# univ_3-2-5-x-rev4.net
KiCad netlist of a schematic drawn in EAGLE
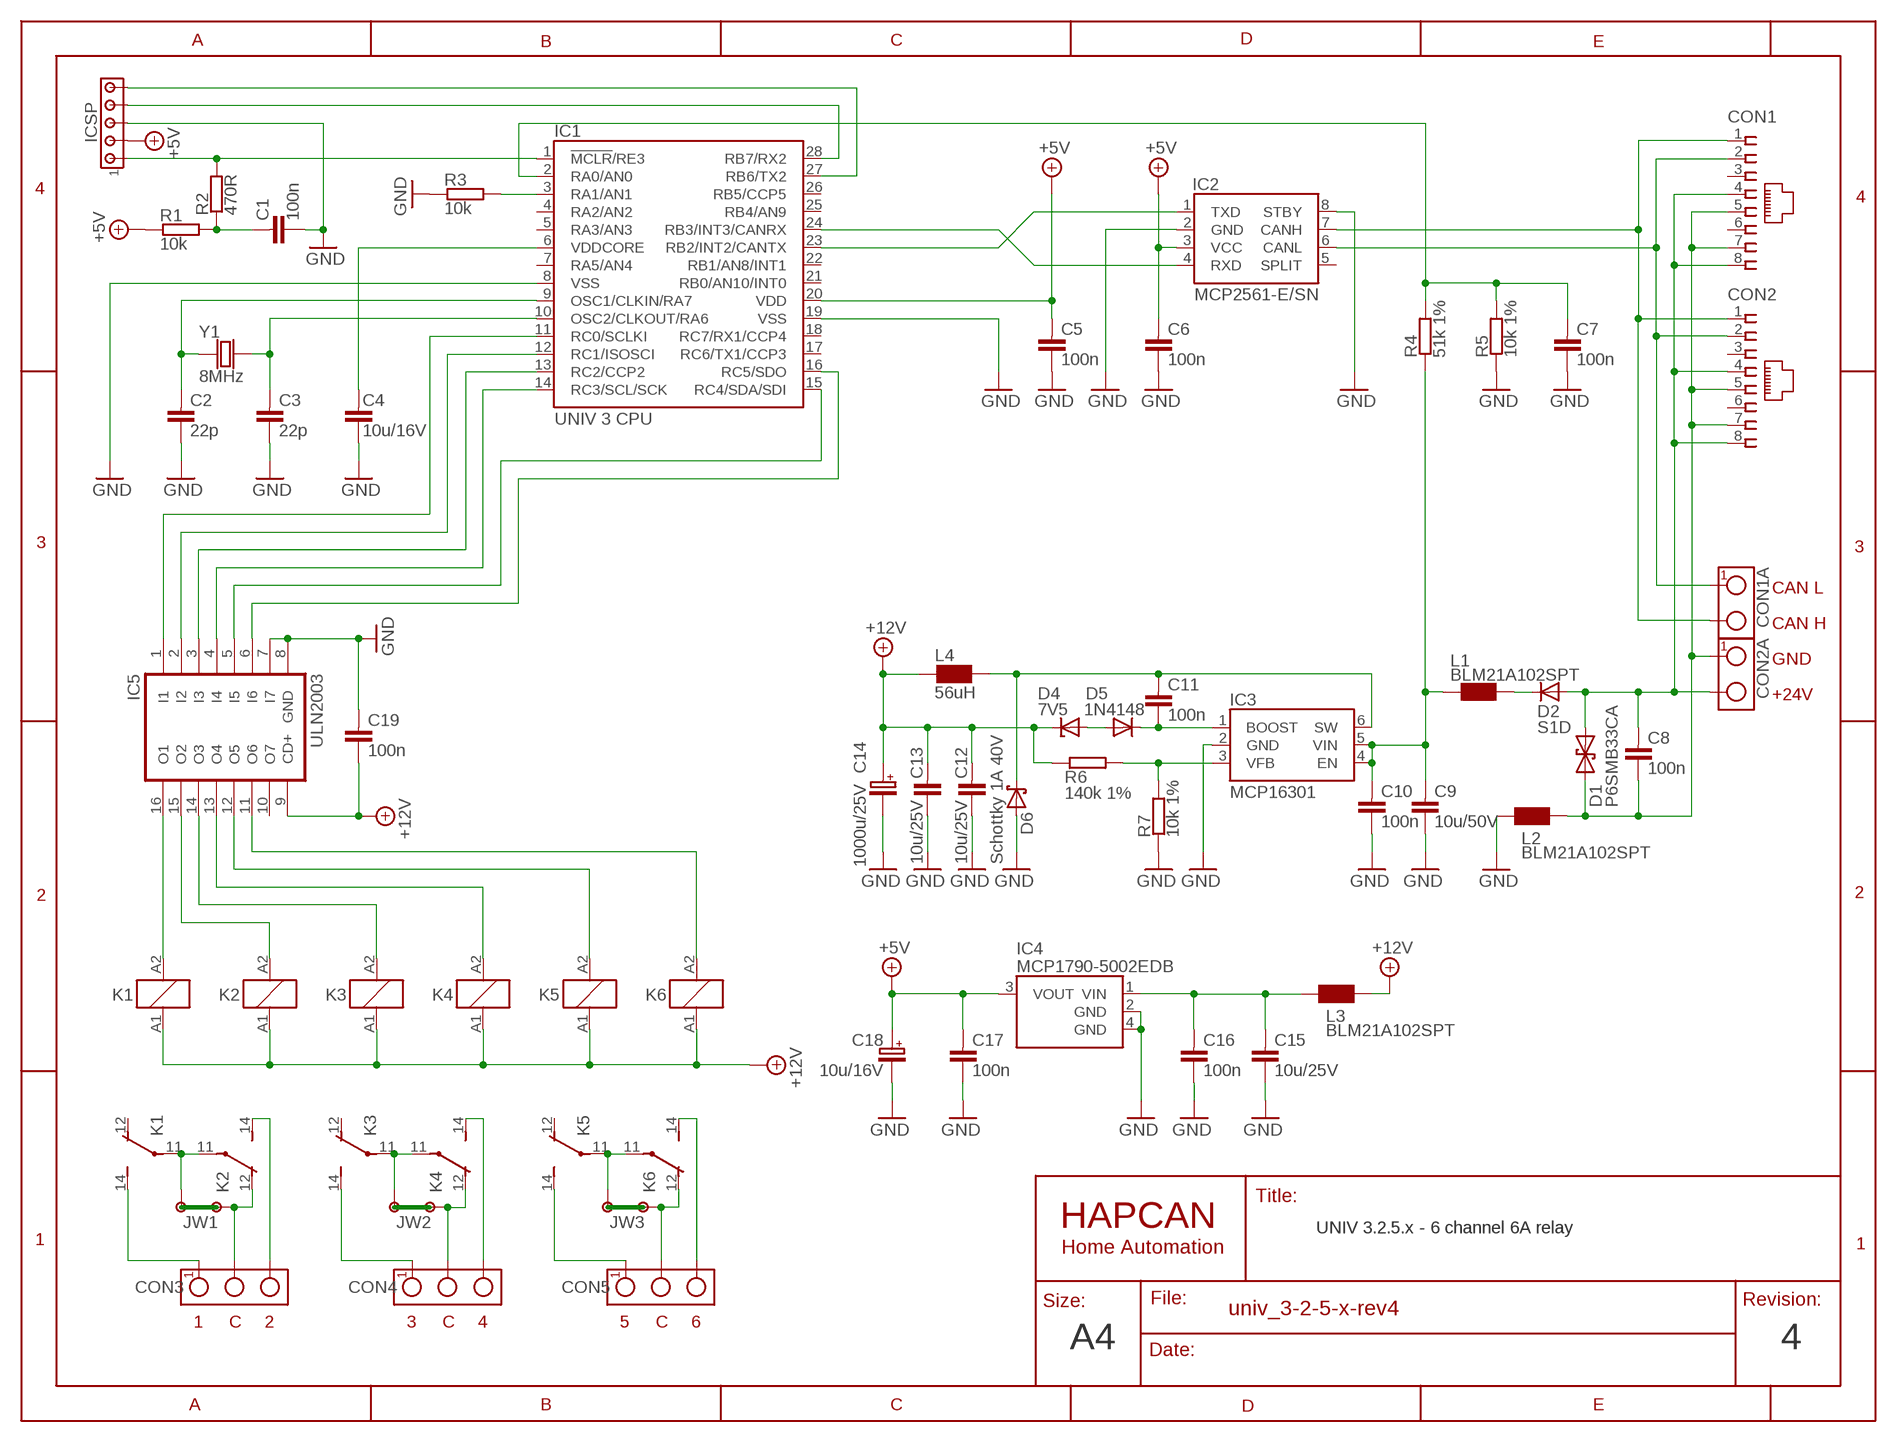
[diagram p0: schematic, sheet 1]

(export (version "E")
  (design (tool "Eeschema 10.0.6"))
  (components
    (comp (ref "1")
      (value "HEADER11X0.9")
      (footprint "eagle-import:SIP-1")
      (libsource (lib "eagle-import") (part "HEADER11X0.9"))
    )
    (comp (ref "2")
      (value "HEADER11X0.9")
      (footprint "eagle-import:SIP-1")
      (libsource (lib "eagle-import") (part "HEADER11X0.9"))
    )
    (comp (ref "3")
      (value "HEADER11X0.9")
      (footprint "eagle-import:SIP-1")
      (libsource (lib "eagle-import") (part "HEADER11X0.9"))
    )
    (comp (ref "C1")
      (value "100n")
      (footprint "eagle-import:0805")
      (libsource (lib "eagle-import") (part "CAPACITOR0805"))
    )
    (comp (ref "C2")
      (value "22p")
      (footprint "eagle-import:0805")
      (libsource (lib "eagle-import") (part "CAPACITOR0805"))
    )
    (comp (ref "C3")
      (value "22p")
      (footprint "eagle-import:0805")
      (libsource (lib "eagle-import") (part "CAPACITOR0805"))
    )
    (comp (ref "C4")
      (value "10u/16V")
      (footprint "eagle-import:0805")
      (libsource (lib "eagle-import") (part "CAPACITOR0805"))
    )
    (comp (ref "C5")
      (value "100n")
      (footprint "eagle-import:0805")
      (libsource (lib "eagle-import") (part "CAPACITOR0805"))
    )
    (comp (ref "C6")
      (value "100n")
      (footprint "eagle-import:0805")
      (libsource (lib "eagle-import") (part "CAPACITOR0805"))
    )
    (comp (ref "C7")
      (value "100n")
      (footprint "eagle-import:0805")
      (libsource (lib "eagle-import") (part "CAPACITOR0805"))
    )
    (comp (ref "C8")
      (value "100n")
      (footprint "eagle-import:0805")
      (libsource (lib "eagle-import") (part "CAPACITOR0805"))
    )
    (comp (ref "C9")
      (value "10u/50V")
      (footprint "eagle-import:1210")
      (libsource (lib "eagle-import") (part "CAPACITOR1210"))
    )
    (comp (ref "C10")
      (value "100n")
      (footprint "eagle-import:0805")
      (libsource (lib "eagle-import") (part "CAPACITOR0805"))
    )
    (comp (ref "C11")
      (value "100n")
      (footprint "eagle-import:0805")
      (libsource (lib "eagle-import") (part "CAPACITOR0805"))
    )
    (comp (ref "C12")
      (value "10u/25V")
      (footprint "eagle-import:1206")
      (libsource (lib "eagle-import") (part "CAPACITOR1206"))
    )
    (comp (ref "C13")
      (value "10u/25V")
      (footprint "eagle-import:1206")
      (libsource (lib "eagle-import") (part "CAPACITOR1206"))
    )
    (comp (ref "C14")
      (value "1000u/25V")
      (footprint "eagle-import:CAP-5X10.5")
      (libsource (lib "eagle-import") (part "CAPACITOR-POLARIZED-5X10.5"))
    )
    (comp (ref "C15")
      (value "10u/25V")
      (footprint "eagle-import:1206")
      (libsource (lib "eagle-import") (part "CAPACITOR1206"))
    )
    (comp (ref "C16")
      (value "100n")
      (footprint "eagle-import:0805")
      (libsource (lib "eagle-import") (part "CAPACITOR0805"))
    )
    (comp (ref "C17")
      (value "100n")
      (footprint "eagle-import:0805")
      (libsource (lib "eagle-import") (part "CAPACITOR0805"))
    )
    (comp (ref "C18")
      (value "10u/16V")
      (footprint "eagle-import:SMC_B")
      (libsource (lib "eagle-import") (part "CAPACITOR-POLARIZED-SMC_B"))
    )
    (comp (ref "C19")
      (value "100n")
      (footprint "eagle-import:0805")
      (libsource (lib "eagle-import") (part "CAPACITOR0805"))
    )
    (comp (ref "CON1")
      (value "RJ45-SOCKET")
      (footprint "eagle-import:RJ45-PCB-SOCKET")
      (libsource (lib "eagle-import") (part "RJ45-SOCKET"))
    )
    (comp (ref "CON1A")
      (value "TERMINAL-2")
      (footprint "eagle-import:ARK2-5X10,5MM")
      (libsource (lib "eagle-import") (part "TERMINAL-2-5X10,5MM"))
    )
    (comp (ref "CON2")
      (value "RJ45-SOCKET")
      (footprint "eagle-import:RJ45-PCB-SOCKET")
      (libsource (lib "eagle-import") (part "RJ45-SOCKET"))
    )
    (comp (ref "CON2A")
      (value "TERMINAL-2")
      (footprint "eagle-import:ARK2-5X10,5MM")
      (libsource (lib "eagle-import") (part "TERMINAL-2-5X10,5MM"))
    )
    (comp (ref "CON3")
      (value "TERMINAL-3-5X10.5MM")
      (footprint "eagle-import:ARK3-5X10.5MM")
      (libsource (lib "eagle-import") (part "TERMINAL-3-5X10.5MM"))
    )
    (comp (ref "CON4")
      (value "TERMINAL-3-5X10.5MM")
      (footprint "eagle-import:ARK3-5X10.5MM")
      (libsource (lib "eagle-import") (part "TERMINAL-3-5X10.5MM"))
    )
    (comp (ref "CON5")
      (value "TERMINAL-3-5X10.5MM")
      (footprint "eagle-import:ARK3-5X10.5MM")
      (libsource (lib "eagle-import") (part "TERMINAL-3-5X10.5MM"))
    )
    (comp (ref "D1")
      (value "P6SMB33CA")
      (footprint "eagle-import:DO-214_TRANSIL2")
      (libsource (lib "eagle-import") (part "DIODE_TRANSIL2"))
    )
    (comp (ref "D2")
      (value "S1D")
      (footprint "eagle-import:DO-214")
      (libsource (lib "eagle-import") (part "DIODE_DO-214"))
    )
    (comp (ref "D4")
      (value "7V5")
      (footprint "eagle-import:SOD-80")
      (libsource (lib "eagle-import") (part "DIODE_ZENER_SOD-80"))
    )
    (comp (ref "D5")
      (value "1N4148")
      (footprint "eagle-import:0805")
      (libsource (lib "eagle-import") (part "DIODE_0805"))
    )
    (comp (ref "D6")
      (value "Schottky 1A 40V")
      (footprint "eagle-import:DO-214")
      (libsource (lib "eagle-import") (part "DIODE_TRANSIL1_DO214"))
    )
    (comp (ref "IC1")
      (value "UNIV 3 CPU")
      (footprint "eagle-import:UNIV3CPU")
      (libsource (lib "eagle-import") (part "UNIV3CPU-I/SO"))
    )
    (comp (ref "IC2")
      (value "MCP2561-E/SN")
      (footprint "eagle-import:SO-08")
      (libsource (lib "eagle-import") (part "MCP2561-E/SN"))
    )
    (comp (ref "IC3")
      (value "MCP16301")
      (footprint "eagle-import:SOT-23-6")
      (libsource (lib "eagle-import") (part "MCP16301SOT23-6"))
    )
    (comp (ref "IC4")
      (value "MCP1790-5002EDB")
      (footprint "eagle-import:SOT-223")
      (libsource (lib "eagle-import") (part "MCP1826SOT223-3"))
    )
    (comp (ref "IC5")
      (value "ULN2003")
      (footprint "eagle-import:SO-16")
      (libsource (lib "eagle-import") (part "ULN2003"))
    )
    (comp (ref "ICSP")
      (value "HEADER5")
      (footprint "eagle-import:SIP-5")
      (libsource (lib "eagle-import") (part "HEADER5"))
    )
    (comp (ref "JW1")
      (value "HEADER11X0.9")
      (footprint "eagle-import:SIP-1")
      (libsource (lib "eagle-import") (part "HEADER11X0.9"))
    )
    (comp (ref "JW2")
      (value "HEADER11X0.9")
      (footprint "eagle-import:SIP-1")
      (libsource (lib "eagle-import") (part "HEADER11X0.9"))
    )
    (comp (ref "JW3")
      (value "HEADER11X0.9")
      (footprint "eagle-import:SIP-1")
      (libsource (lib "eagle-import") (part "HEADER11X0.9"))
    )
    (comp (ref "K1")
      (value "RELAY_SNR_SPDTV")
      (footprint "eagle-import:RELAY_SNR_SPDT_V")
      (libsource (lib "eagle-import") (part "RELAY_SNR_SPDTV"))
    )
    (comp (ref "K2")
      (value "RELAY_SNR_SPDTV")
      (footprint "eagle-import:RELAY_SNR_SPDT_V")
      (libsource (lib "eagle-import") (part "RELAY_SNR_SPDTV"))
    )
    (comp (ref "K3")
      (value "RELAY_SNR_SPDTV")
      (footprint "eagle-import:RELAY_SNR_SPDT_V")
      (libsource (lib "eagle-import") (part "RELAY_SNR_SPDTV"))
    )
    (comp (ref "K4")
      (value "RELAY_SNR_SPDTV")
      (footprint "eagle-import:RELAY_SNR_SPDT_V")
      (libsource (lib "eagle-import") (part "RELAY_SNR_SPDTV"))
    )
    (comp (ref "K5")
      (value "RELAY_SNR_SPDTV")
      (footprint "eagle-import:RELAY_SNR_SPDT_V")
      (libsource (lib "eagle-import") (part "RELAY_SNR_SPDTV"))
    )
    (comp (ref "K6")
      (value "RELAY_SNR_SPDTV")
      (footprint "eagle-import:RELAY_SNR_SPDT_V")
      (libsource (lib "eagle-import") (part "RELAY_SNR_SPDTV"))
    )
    (comp (ref "L1")
      (value "BLM21A102SPT")
      (footprint "eagle-import:0805")
      (libsource (lib "eagle-import") (part "CHOKE0805"))
    )
    (comp (ref "L2")
      (value "BLM21A102SPT")
      (footprint "eagle-import:0805")
      (libsource (lib "eagle-import") (part "CHOKE0805"))
    )
    (comp (ref "L3")
      (value "BLM21A102SPT")
      (footprint "eagle-import:0805")
      (libsource (lib "eagle-import") (part "CHOKE0805"))
    )
    (comp (ref "L4")
      (value "56uH")
      (footprint "eagle-import:CHOKE-DER0705")
      (libsource (lib "eagle-import") (part "CHOKEDER0705"))
    )
    (comp (ref "R1")
      (value "10k")
      (footprint "eagle-import:0805")
      (libsource (lib "eagle-import") (part "RESISTOR0805"))
    )
    (comp (ref "R2")
      (value "470R")
      (footprint "eagle-import:0805")
      (libsource (lib "eagle-import") (part "RESISTOR0805"))
    )
    (comp (ref "R3")
      (value "10k")
      (footprint "eagle-import:0805")
      (libsource (lib "eagle-import") (part "RESISTOR0805"))
    )
    (comp (ref "R4")
      (value "51k 1%")
      (footprint "eagle-import:0805")
      (libsource (lib "eagle-import") (part "RESISTOR0805"))
    )
    (comp (ref "R5")
      (value "10k 1%")
      (footprint "eagle-import:0805")
      (libsource (lib "eagle-import") (part "RESISTOR0805"))
    )
    (comp (ref "R6")
      (value "140k 1%")
      (footprint "eagle-import:0805")
      (libsource (lib "eagle-import") (part "RESISTOR0805"))
    )
    (comp (ref "R7")
      (value "10k 1%")
      (footprint "eagle-import:0805")
      (libsource (lib "eagle-import") (part "RESISTOR0805"))
    )
    (comp (ref "Y1")
      (value "8MHz")
      (footprint "eagle-import:CRYSTAL-HC49V")
      (libsource (lib "eagle-import") (part "CRYSTAL-HC49V"))
    )
  )
  (nets
    (net (code "1") (name "+5V") (class "Default")
      (node (ref "C17") (pin "1") (pinfunction "1_1") (pintype "passive"))
      (node (ref "C18") (pin "+") (pinfunction "1_+") (pintype "passive"))
      (node (ref "C5") (pin "1") (pinfunction "1_1") (pintype "passive"))
      (node (ref "C6") (pin "1") (pinfunction "1_1") (pintype "passive"))
      (node (ref "IC1") (pin "20") (pinfunction "VDD_20") (pintype "bidirectional"))
      (node (ref "IC2") (pin "3") (pinfunction "VCC_3") (pintype "bidirectional"))
      (node (ref "IC4") (pin "3") (pinfunction "VOUT_3") (pintype "bidirectional"))
      (node (ref "ICSP") (pin "2") (pinfunction "2_2") (pintype "passive"))
      (node (ref "R1") (pin "1") (pinfunction "1_1") (pintype "passive"))
    )
    (net (code "2") (name "+12V") (class "Default")
      (node (ref "C12") (pin "1") (pinfunction "1_1") (pintype "passive"))
      (node (ref "C13") (pin "1") (pinfunction "1_1") (pintype "passive"))
      (node (ref "C14") (pin "+") (pinfunction "1_+") (pintype "passive"))
      (node (ref "C19") (pin "2") (pinfunction "2_2") (pintype "passive"))
      (node (ref "D4") (pin "C") (pinfunction "C_C") (pintype "passive"))
      (node (ref "IC5") (pin "9") (pinfunction "CD+_9") (pintype "passive"))
      (node (ref "K1") (pin "A1") (pinfunction "1_A1") (pintype "passive"))
      (node (ref "K2") (pin "A1") (pinfunction "1_A1") (pintype "passive"))
      (node (ref "K3") (pin "A1") (pinfunction "1_A1") (pintype "passive"))
      (node (ref "K4") (pin "A1") (pinfunction "1_A1") (pintype "passive"))
      (node (ref "K5") (pin "A1") (pinfunction "1_A1") (pintype "passive"))
      (node (ref "K6") (pin "A1") (pinfunction "1_A1") (pintype "passive"))
      (node (ref "L3") (pin "2") (pinfunction "2_2") (pintype "passive"))
      (node (ref "L4") (pin "1") (pinfunction "1_1") (pintype "passive"))
      (node (ref "R6") (pin "1") (pinfunction "1_1") (pintype "passive"))
    )
    (net (code "4") (name "GND") (class "Default")
      (node (ref "C1") (pin "2") (pinfunction "2_2") (pintype "passive"))
      (node (ref "C10") (pin "2") (pinfunction "2_2") (pintype "passive"))
      (node (ref "C12") (pin "2") (pinfunction "2_2") (pintype "passive"))
      (node (ref "C13") (pin "2") (pinfunction "2_2") (pintype "passive"))
      (node (ref "C14") (pin "-") (pinfunction "2_-") (pintype "passive"))
      (node (ref "C15") (pin "2") (pinfunction "2_2") (pintype "passive"))
      (node (ref "C16") (pin "2") (pinfunction "2_2") (pintype "passive"))
      (node (ref "C17") (pin "2") (pinfunction "2_2") (pintype "passive"))
      (node (ref "C18") (pin "-") (pinfunction "2_-") (pintype "passive"))
      (node (ref "C19") (pin "1") (pinfunction "1_1") (pintype "passive"))
      (node (ref "C2") (pin "2") (pinfunction "2_2") (pintype "passive"))
      (node (ref "C3") (pin "2") (pinfunction "2_2") (pintype "passive"))
      (node (ref "C4") (pin "2") (pinfunction "2_2") (pintype "passive"))
      (node (ref "C5") (pin "2") (pinfunction "2_2") (pintype "passive"))
      (node (ref "C6") (pin "2") (pinfunction "2_2") (pintype "passive"))
      (node (ref "C7") (pin "2") (pinfunction "2_2") (pintype "passive"))
      (node (ref "C9") (pin "2") (pinfunction "2_2") (pintype "passive"))
      (node (ref "D6") (pin "A") (pinfunction "A_A") (pintype "passive"))
      (node (ref "IC1") (pin "19") (pinfunction "VSS_19") (pintype "bidirectional"))
      (node (ref "IC1") (pin "8") (pinfunction "VSS_8") (pintype "bidirectional"))
      (node (ref "IC2") (pin "2") (pinfunction "GND_2") (pintype "bidirectional"))
      (node (ref "IC2") (pin "8") (pinfunction "STBY_8") (pintype "bidirectional"))
      (node (ref "IC3") (pin "2") (pinfunction "GND_2") (pintype "bidirectional"))
      (node (ref "IC4") (pin "2") (pinfunction "GND_2") (pintype "bidirectional"))
      (node (ref "IC4") (pin "4") (pinfunction "GND_4") (pintype "bidirectional"))
      (node (ref "IC5") (pin "7") (pinfunction "I7_7") (pintype "input"))
      (node (ref "IC5") (pin "8") (pinfunction "GND_8") (pintype "power_in"))
      (node (ref "ICSP") (pin "3") (pinfunction "3_3") (pintype "passive"))
      (node (ref "L2") (pin "1") (pinfunction "1_1") (pintype "passive"))
      (node (ref "R3") (pin "1") (pinfunction "1_1") (pintype "passive"))
      (node (ref "R5") (pin "1") (pinfunction "1_1") (pintype "passive"))
      (node (ref "R7") (pin "1") (pinfunction "1_1") (pintype "passive"))
    )
    (net (code "5") (name "Net-(C1-Pad1)") (class "Default")
      (node (ref "C1") (pin "1") (pinfunction "1_1") (pintype "passive"))
      (node (ref "R1") (pin "2") (pinfunction "2_2") (pintype "passive"))
      (node (ref "R2") (pin "1") (pinfunction "1_1") (pintype "passive"))
    )
    (net (code "6") (name "Net-(D1-1)") (class "Default")
      (node (ref "C8") (pin "2") (pinfunction "2_2") (pintype "passive"))
      (node (ref "CON1") (pin "5") (pinfunction "5_5") (pintype "passive"))
      (node (ref "CON1") (pin "7") (pinfunction "7_7") (pintype "passive"))
      (node (ref "CON2") (pin "5") (pinfunction "5_5") (pintype "passive"))
      (node (ref "CON2") (pin "7") (pinfunction "7_7") (pintype "passive"))
      (node (ref "CON2A") (pin "1") (pinfunction "1_1") (pintype "passive"))
      (node (ref "D1") (pin "A") (pinfunction "1_A") (pintype "passive"))
      (node (ref "L2") (pin "2") (pinfunction "2_2") (pintype "passive"))
    )
    (net (code "7") (name "Net-(D1-2)") (class "Default")
      (node (ref "C8") (pin "1") (pinfunction "1_1") (pintype "passive"))
      (node (ref "CON1") (pin "4") (pinfunction "4_4") (pintype "passive"))
      (node (ref "CON1") (pin "8") (pinfunction "8_8") (pintype "passive"))
      (node (ref "CON2") (pin "4") (pinfunction "4_4") (pintype "passive"))
      (node (ref "CON2") (pin "8") (pinfunction "8_8") (pintype "passive"))
      (node (ref "CON2A") (pin "2") (pinfunction "2_2") (pintype "passive"))
      (node (ref "D1") (pin "C") (pinfunction "2_C") (pintype "passive"))
      (node (ref "D2") (pin "A") (pinfunction "A_A") (pintype "passive"))
    )
    (net (code "8") (name "Net-(D2-PadC)") (class "Default")
      (node (ref "D2") (pin "C") (pinfunction "C_C") (pintype "passive"))
      (node (ref "L1") (pin "2") (pinfunction "2_2") (pintype "passive"))
    )
    (net (code "9") (name "Net-(D5-A)") (class "Default")
      (node (ref "D4") (pin "A") (pinfunction "A_A") (pintype "passive"))
      (node (ref "D5") (pin "2") (pinfunction "A_2") (pintype "passive"))
    )
    (net (code "10") (name "Net-(D5-C)") (class "Default")
      (node (ref "C11") (pin "2") (pinfunction "2_2") (pintype "passive"))
      (node (ref "D5") (pin "1") (pinfunction "C_1") (pintype "passive"))
      (node (ref "IC3") (pin "1") (pinfunction "BOOST_1") (pintype "bidirectional"))
    )
    (net (code "11") (name "Net-(IC1-OSC1{slash}CLKIN{slash}RA7)") (class "Default")
      (node (ref "C2") (pin "1") (pinfunction "1_1") (pintype "passive"))
      (node (ref "IC1") (pin "9") (pinfunction "OSC1/CLKIN/RA7_9") (pintype "bidirectional"))
      (node (ref "Y1") (pin "1") (pinfunction "1_1") (pintype "passive"))
    )
    (net (code "12") (name "Net-(IC1-OSC2{slash}CLKOUT{slash}RA6)") (class "Default")
      (node (ref "C3") (pin "1") (pinfunction "1_1") (pintype "passive"))
      (node (ref "IC1") (pin "10") (pinfunction "OSC2/CLKOUT/RA6_10") (pintype "bidirectional"))
      (node (ref "Y1") (pin "2") (pinfunction "2_2") (pintype "passive"))
    )
    (net (code "13") (name "Net-(IC1-RA0{slash}AN0)") (class "Default")
      (node (ref "C7") (pin "1") (pinfunction "1_1") (pintype "passive"))
      (node (ref "IC1") (pin "2") (pinfunction "RA0/AN0_2") (pintype "bidirectional"))
      (node (ref "R4") (pin "2") (pinfunction "2_2") (pintype "passive"))
      (node (ref "R5") (pin "2") (pinfunction "2_2") (pintype "passive"))
    )
    (net (code "14") (name "Net-(IC1-RA1{slash}AN1)") (class "Default")
      (node (ref "IC1") (pin "3") (pinfunction "RA1/AN1_3") (pintype "bidirectional"))
      (node (ref "R3") (pin "2") (pinfunction "2_2") (pintype "passive"))
    )
    (net (code "15") (name "Net-(IC1-RB2{slash}INT2{slash}CANTX)") (class "Default")
      (node (ref "IC1") (pin "23") (pinfunction "RB2/INT2/CANTX_23") (pintype "bidirectional"))
      (node (ref "IC2") (pin "1") (pinfunction "TXD_1") (pintype "bidirectional"))
    )
    (net (code "16") (name "Net-(IC1-RB3{slash}INT3{slash}CANRX)") (class "Default")
      (node (ref "IC1") (pin "24") (pinfunction "RB3/INT3/CANRX_24") (pintype "bidirectional"))
      (node (ref "IC2") (pin "4") (pinfunction "RXD_4") (pintype "bidirectional"))
    )
    (net (code "17") (name "Net-(IC1-RB6{slash}TX2)") (class "Default")
      (node (ref "IC1") (pin "27") (pinfunction "RB6/TX2_27") (pintype "bidirectional"))
      (node (ref "ICSP") (pin "5") (pinfunction "5_5") (pintype "passive"))
    )
    (net (code "18") (name "Net-(IC1-RB7{slash}RX2)") (class "Default")
      (node (ref "IC1") (pin "28") (pinfunction "RB7/RX2_28") (pintype "bidirectional"))
      (node (ref "ICSP") (pin "4") (pinfunction "4_4") (pintype "passive"))
    )
    (net (code "19") (name "Net-(IC1-RC0{slash}SCLKI)") (class "Default")
      (node (ref "IC1") (pin "11") (pinfunction "RC0/SCLKI_11") (pintype "bidirectional"))
      (node (ref "IC5") (pin "1") (pinfunction "I1_1") (pintype "input"))
    )
    (net (code "20") (name "Net-(IC1-RC1{slash}ISOSCI)") (class "Default")
      (node (ref "IC1") (pin "12") (pinfunction "RC1/ISOSCI_12") (pintype "bidirectional"))
      (node (ref "IC5") (pin "2") (pinfunction "I2_2") (pintype "input"))
    )
    (net (code "21") (name "Net-(IC1-RC2{slash}CCP2)") (class "Default")
      (node (ref "IC1") (pin "13") (pinfunction "RC2/CCP2_13") (pintype "bidirectional"))
      (node (ref "IC5") (pin "3") (pinfunction "I3_3") (pintype "input"))
    )
    (net (code "22") (name "Net-(IC1-RC3{slash}SCL{slash}SCK)") (class "Default")
      (node (ref "IC1") (pin "14") (pinfunction "RC3/SCL/SCK_14") (pintype "bidirectional"))
      (node (ref "IC5") (pin "4") (pinfunction "I4_4") (pintype "input"))
    )
    (net (code "23") (name "Net-(IC1-RC4{slash}SDA{slash}SDI)") (class "Default")
      (node (ref "IC1") (pin "15") (pinfunction "RC4/SDA/SDI_15") (pintype "bidirectional"))
      (node (ref "IC5") (pin "5") (pinfunction "I5_5") (pintype "input"))
    )
    (net (code "24") (name "Net-(IC1-RC5{slash}SDO)") (class "Default")
      (node (ref "IC1") (pin "16") (pinfunction "RC5/SDO_16") (pintype "bidirectional"))
      (node (ref "IC5") (pin "6") (pinfunction "I6_6") (pintype "input"))
    )
    (net (code "25") (name "Net-(IC1-VDDCORE)") (class "Default")
      (node (ref "C4") (pin "1") (pinfunction "1_1") (pintype "passive"))
      (node (ref "IC1") (pin "6") (pinfunction "VDDCORE_6") (pintype "bidirectional"))
    )
    (net (code "26") (name "Net-(IC1-~{MCLR}{slash}RE3)") (class "Default")
      (node (ref "IC1") (pin "1") (pinfunction "~{MCLR}/RE3_1") (pintype "bidirectional"))
      (node (ref "ICSP") (pin "1") (pinfunction "1_1") (pintype "passive"))
      (node (ref "R2") (pin "2") (pinfunction "2_2") (pintype "passive"))
    )
    (net (code "27") (name "Net-(IC2-CANH)") (class "Default")
      (node (ref "CON1") (pin "1") (pinfunction "1_1") (pintype "passive"))
      (node (ref "CON1A") (pin "2") (pinfunction "2_2") (pintype "passive"))
      (node (ref "CON2") (pin "1") (pinfunction "1_1") (pintype "passive"))
      (node (ref "IC2") (pin "7") (pinfunction "CANH_7") (pintype "bidirectional"))
    )
    (net (code "28") (name "Net-(IC2-CANL)") (class "Default")
      (node (ref "CON1") (pin "2") (pinfunction "2_2") (pintype "passive"))
      (node (ref "CON1A") (pin "1") (pinfunction "1_1") (pintype "passive"))
      (node (ref "CON2") (pin "2") (pinfunction "2_2") (pintype "passive"))
      (node (ref "IC2") (pin "6") (pinfunction "CANL_6") (pintype "bidirectional"))
    )
    (net (code "29") (name "Net-(IC3-EN)") (class "Default")
      (node (ref "C10") (pin "1") (pinfunction "1_1") (pintype "passive"))
      (node (ref "C9") (pin "1") (pinfunction "1_1") (pintype "passive"))
      (node (ref "IC3") (pin "4") (pinfunction "EN_4") (pintype "bidirectional"))
      (node (ref "IC3") (pin "5") (pinfunction "VIN_5") (pintype "bidirectional"))
      (node (ref "L1") (pin "1") (pinfunction "1_1") (pintype "passive"))
      (node (ref "R4") (pin "1") (pinfunction "1_1") (pintype "passive"))
    )
    (net (code "30") (name "Net-(IC3-SW)") (class "Default")
      (node (ref "C11") (pin "1") (pinfunction "1_1") (pintype "passive"))
      (node (ref "D6") (pin "C") (pinfunction "C_C") (pintype "passive"))
      (node (ref "IC3") (pin "6") (pinfunction "SW_6") (pintype "bidirectional"))
      (node (ref "L4") (pin "2") (pinfunction "2_2") (pintype "passive"))
    )
    (net (code "31") (name "Net-(IC3-VFB)") (class "Default")
      (node (ref "IC3") (pin "3") (pinfunction "VFB_3") (pintype "bidirectional"))
      (node (ref "R6") (pin "2") (pinfunction "2_2") (pintype "passive"))
      (node (ref "R7") (pin "2") (pinfunction "2_2") (pintype "passive"))
    )
    (net (code "32") (name "Net-(IC4-VIN)") (class "Default")
      (node (ref "C15") (pin "1") (pinfunction "1_1") (pintype "passive"))
      (node (ref "C16") (pin "1") (pinfunction "1_1") (pintype "passive"))
      (node (ref "IC4") (pin "1") (pinfunction "VIN_1") (pintype "bidirectional"))
      (node (ref "L3") (pin "1") (pinfunction "1_1") (pintype "passive"))
    )
    (net (code "33") (name "Net-(IC5-O1)") (class "Default")
      (node (ref "IC5") (pin "16") (pinfunction "O1_16") (pintype "open_collector"))
      (node (ref "K1") (pin "A2") (pinfunction "2_A2") (pintype "passive"))
    )
    (net (code "34") (name "Net-(IC5-O2)") (class "Default")
      (node (ref "IC5") (pin "15") (pinfunction "O2_15") (pintype "open_collector"))
      (node (ref "K2") (pin "A2") (pinfunction "2_A2") (pintype "passive"))
    )
    (net (code "35") (name "Net-(IC5-O3)") (class "Default")
      (node (ref "IC5") (pin "14") (pinfunction "O3_14") (pintype "open_collector"))
      (node (ref "K3") (pin "A2") (pinfunction "2_A2") (pintype "passive"))
    )
    (net (code "36") (name "Net-(IC5-O4)") (class "Default")
      (node (ref "IC5") (pin "13") (pinfunction "O4_13") (pintype "open_collector"))
      (node (ref "K4") (pin "A2") (pinfunction "2_A2") (pintype "passive"))
    )
    (net (code "37") (name "Net-(IC5-O5)") (class "Default")
      (node (ref "IC5") (pin "12") (pinfunction "O5_12") (pintype "open_collector"))
      (node (ref "K5") (pin "A2") (pinfunction "2_A2") (pintype "passive"))
    )
    (net (code "38") (name "Net-(IC5-O6)") (class "Default")
      (node (ref "IC5") (pin "11") (pinfunction "O6_11") (pintype "open_collector"))
      (node (ref "K6") (pin "A2") (pinfunction "2_A2") (pintype "passive"))
    )
    (net (code "39") (name "Net-(K1B-COM)") (class "Default")
      (node (ref "JW1") (pin "1") (pinfunction "1_1") (pintype "passive"))
      (node (ref "K1") (pin "11") (pinfunction "COM_11") (pintype "passive"))
      (node (ref "K2") (pin "11") (pinfunction "COM_11") (pintype "passive"))
    )
    (net (code "40") (name "Net-(K1B-NO)") (class "Default")
      (node (ref "CON3") (pin "1") (pinfunction "1_1") (pintype "passive"))
      (node (ref "K1") (pin "14") (pinfunction "NO_14") (pintype "passive"))
    )
    (net (code "41") (name "Net-(K2B-NC)") (class "Default")
      (node (ref "1") (pin "1") (pinfunction "1_1") (pintype "passive"))
      (node (ref "CON3") (pin "2") (pinfunction "2_2") (pintype "passive"))
      (node (ref "K2") (pin "12") (pinfunction "NC_12") (pintype "passive"))
    )
    (net (code "42") (name "Net-(K2B-NO)") (class "Default")
      (node (ref "CON3") (pin "3") (pinfunction "3_3") (pintype "passive"))
      (node (ref "K2") (pin "14") (pinfunction "NO_14") (pintype "passive"))
    )
    (net (code "43") (name "Net-(K3B-COM)") (class "Default")
      (node (ref "JW2") (pin "1") (pinfunction "1_1") (pintype "passive"))
      (node (ref "K3") (pin "11") (pinfunction "COM_11") (pintype "passive"))
      (node (ref "K4") (pin "11") (pinfunction "COM_11") (pintype "passive"))
    )
    (net (code "44") (name "Net-(K3B-NO)") (class "Default")
      (node (ref "CON4") (pin "1") (pinfunction "1_1") (pintype "passive"))
      (node (ref "K3") (pin "14") (pinfunction "NO_14") (pintype "passive"))
    )
    (net (code "45") (name "Net-(K4B-NC)") (class "Default")
      (node (ref "2") (pin "1") (pinfunction "1_1") (pintype "passive"))
      (node (ref "CON4") (pin "2") (pinfunction "2_2") (pintype "passive"))
      (node (ref "K4") (pin "12") (pinfunction "NC_12") (pintype "passive"))
    )
    (net (code "46") (name "Net-(K4B-NO)") (class "Default")
      (node (ref "CON4") (pin "3") (pinfunction "3_3") (pintype "passive"))
      (node (ref "K4") (pin "14") (pinfunction "NO_14") (pintype "passive"))
    )
    (net (code "47") (name "Net-(K5B-COM)") (class "Default")
      (node (ref "JW3") (pin "1") (pinfunction "1_1") (pintype "passive"))
      (node (ref "K5") (pin "11") (pinfunction "COM_11") (pintype "passive"))
      (node (ref "K6") (pin "11") (pinfunction "COM_11") (pintype "passive"))
    )
    (net (code "48") (name "Net-(K5B-NO)") (class "Default")
      (node (ref "CON5") (pin "1") (pinfunction "1_1") (pintype "passive"))
      (node (ref "K5") (pin "14") (pinfunction "NO_14") (pintype "passive"))
    )
    (net (code "49") (name "Net-(K6B-NC)") (class "Default")
      (node (ref "3") (pin "1") (pinfunction "1_1") (pintype "passive"))
      (node (ref "CON5") (pin "2") (pinfunction "2_2") (pintype "passive"))
      (node (ref "K6") (pin "12") (pinfunction "NC_12") (pintype "passive"))
    )
    (net (code "50") (name "Net-(K6B-NO)") (class "Default")
      (node (ref "CON5") (pin "3") (pinfunction "3_3") (pintype "passive"))
      (node (ref "K6") (pin "14") (pinfunction "NO_14") (pintype "passive"))
    )
    (net (code "51") (name "unconnected-(CON1-Pad3)") (class "Default")
      (node (ref "CON1") (pin "3") (pinfunction "3_3") (pintype "passive"))
    )
    (net (code "52") (name "unconnected-(CON1-Pad6)") (class "Default")
      (node (ref "CON1") (pin "6") (pinfunction "6_6") (pintype "passive"))
    )
    (net (code "53") (name "unconnected-(CON2-Pad3)") (class "Default")
      (node (ref "CON2") (pin "3") (pinfunction "3_3") (pintype "passive"))
    )
    (net (code "54") (name "unconnected-(CON2-Pad6)") (class "Default")
      (node (ref "CON2") (pin "6") (pinfunction "6_6") (pintype "passive"))
    )
    (net (code "55") (name "unconnected-(IC1-RA2{slash}AN2-Pad4)") (class "Default")
      (node (ref "IC1") (pin "4") (pinfunction "RA2/AN2_4") (pintype "bidirectional"))
    )
    (net (code "56") (name "unconnected-(IC1-RA3{slash}AN3-Pad5)") (class "Default")
      (node (ref "IC1") (pin "5") (pinfunction "RA3/AN3_5") (pintype "bidirectional"))
    )
    (net (code "57") (name "unconnected-(IC1-RA5{slash}AN4-Pad7)") (class "Default")
      (node (ref "IC1") (pin "7") (pinfunction "RA5/AN4_7") (pintype "bidirectional"))
    )
    (net (code "58") (name "unconnected-(IC1-RB0{slash}AN10{slash}INT0-Pad21)") (class "Default")
      (node (ref "IC1") (pin "21") (pinfunction "RB0/AN10/INT0_21") (pintype "bidirectional"))
    )
    (net (code "59") (name "unconnected-(IC1-RB1{slash}AN8{slash}INT1-Pad22)") (class "Default")
      (node (ref "IC1") (pin "22") (pinfunction "RB1/AN8/INT1_22") (pintype "bidirectional"))
    )
    (net (code "60") (name "unconnected-(IC1-RB4{slash}AN9-Pad25)") (class "Default")
      (node (ref "IC1") (pin "25") (pinfunction "RB4/AN9_25") (pintype "bidirectional"))
    )
    (net (code "61") (name "unconnected-(IC1-RB5{slash}CCP5-Pad26)") (class "Default")
      (node (ref "IC1") (pin "26") (pinfunction "RB5/CCP5_26") (pintype "bidirectional"))
    )
    (net (code "62") (name "unconnected-(IC1-RC6{slash}TX1{slash}CCP3-Pad17)") (class "Default")
      (node (ref "IC1") (pin "17") (pinfunction "RC6/TX1/CCP3_17") (pintype "bidirectional"))
    )
    (net (code "63") (name "unconnected-(IC1-RC7{slash}RX1{slash}CCP4-Pad18)") (class "Default")
      (node (ref "IC1") (pin "18") (pinfunction "RC7/RX1/CCP4_18") (pintype "bidirectional"))
    )
    (net (code "64") (name "unconnected-(IC2-SPLIT-Pad5)") (class "Default")
      (node (ref "IC2") (pin "5") (pinfunction "SPLIT_5") (pintype "bidirectional"))
    )
    (net (code "65") (name "unconnected-(IC5-O7-Pad10)") (class "Default")
      (node (ref "IC5") (pin "10") (pinfunction "O7_10") (pintype "open_collector"))
    )
    (net (code "66") (name "unconnected-(K1B-NC-Pad12)") (class "Default")
      (node (ref "K1") (pin "12") (pinfunction "NC_12") (pintype "passive"))
    )
    (net (code "67") (name "unconnected-(K3B-NC-Pad12)") (class "Default")
      (node (ref "K3") (pin "12") (pinfunction "NC_12") (pintype "passive"))
    )
    (net (code "68") (name "unconnected-(K5B-NC-Pad12)") (class "Default")
      (node (ref "K5") (pin "12") (pinfunction "NC_12") (pintype "passive"))
    )
  )
)
